# Oplader.net
KiCad netlist of a schematic drawn in Altium Designer
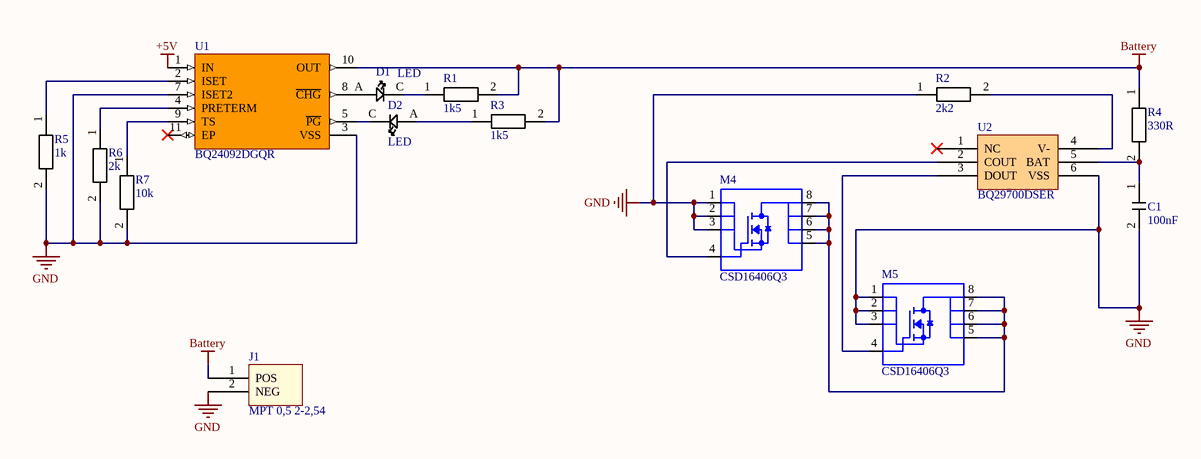
[diagram p0: Oplader.SchDoc]

(export (version "E")
  (design (tool "Eeschema 10.0.6"))
  (components
    (comp (ref "C1") (value "100nF") (footprint "0603") (libsource (lib "condensator") (part "Condensator")))
    (comp (ref "D1") (value "LED") (footprint "LED") (libsource (lib "Schlib1") (part "LED")))
    (comp (ref "D2") (value "LED") (footprint "LED") (libsource (lib "Schlib1") (part "LED")))
    (comp (ref "J1")
      (value "MPT 0,5 2-2,54")
      (footprint "MPT 0,5 2-2,54")
      (libsource (lib "Schlib1") (part "MPT 0,5 2-2,54"))
    )
    (comp (ref "M4")
      (value "CSD16406Q3")
      (footprint "CSD16406Q3")
      (libsource (lib "Schlib1") (part "CSD16406Q3"))
    )
    (comp (ref "M5")
      (value "CSD16406Q3")
      (footprint "CSD16406Q3")
      (libsource (lib "Schlib1") (part "CSD16406Q3"))
    )
    (comp (ref "R1") (value "1k5") (footprint "0603") (libsource (lib "weerstand") (part "weerstand")))
    (comp (ref "R2") (value "2k2") (footprint "0603") (libsource (lib "weerstand") (part "weerstand")))
    (comp (ref "R3") (value "1k5") (footprint "0603") (libsource (lib "weerstand") (part "weerstand")))
    (comp (ref "R4") (value "330R") (footprint "0603") (libsource (lib "weerstand") (part "weerstand")))
    (comp (ref "R5") (value "1k") (footprint "0603") (libsource (lib "weerstand") (part "weerstand")))
    (comp (ref "R6") (value "2k") (footprint "0603") (libsource (lib "weerstand") (part "weerstand")))
    (comp (ref "R7") (value "10k") (footprint "0603") (libsource (lib "weerstand") (part "weerstand")))
    (comp (ref "U1")
      (value "BQ24092DGQR")
      (footprint "BQ24092DGQR")
      (libsource (lib "Schlib1") (part "BQ24092DGQR"))
    )
    (comp (ref "U2")
      (value "BQ29700DSER")
      (footprint "BQ29700DSER")
      (libsource (lib "Schlib1") (part "BQ29700DSER"))
    )
  )
  (nets
    (net (code "1") (name "+5V") (class "Default")
      (node (ref "U1") (pin "1") (pinfunction "IN_1") (pintype "input"))
    )
    (net (code "2") (name "Battery") (class "Default")
      (node (ref "J1") (pin "1") (pinfunction "POS_1") (pintype "passive"))
      (node (ref "R1") (pin "2") (pinfunction "G_2") (pintype "passive"))
      (node (ref "R3") (pin "2") (pinfunction "G_2") (pintype "passive"))
      (node (ref "R4") (pin "1") (pinfunction "1_1") (pintype "passive"))
      (node (ref "U1") (pin "10") (pinfunction "OUT_10") (pintype "output"))
    )
    (net (code "3") (name "GND") (class "Default")
      (node (ref "C1") (pin "2") (pinfunction "G_2") (pintype "passive"))
      (node (ref "J1") (pin "2") (pinfunction "NEG_2") (pintype "passive"))
      (node (ref "M4") (pin "1") (pinfunction "S_1_1") (pintype "passive"))
      (node (ref "M4") (pin "2") (pinfunction "S_2_2") (pintype "passive"))
      (node (ref "M4") (pin "3") (pinfunction "S_3_3") (pintype "passive"))
      (node (ref "M5") (pin "1") (pinfunction "S_1_1") (pintype "passive"))
      (node (ref "M5") (pin "2") (pinfunction "S_2_2") (pintype "passive"))
      (node (ref "M5") (pin "3") (pinfunction "S_3_3") (pintype "passive"))
      (node (ref "R2") (pin "1") (pinfunction "1_1") (pintype "passive"))
      (node (ref "R5") (pin "2") (pinfunction "G_2") (pintype "passive"))
      (node (ref "R6") (pin "2") (pinfunction "G_2") (pintype "passive"))
      (node (ref "R7") (pin "2") (pinfunction "G_2") (pintype "passive"))
      (node (ref "U1") (pin "3") (pinfunction "VSS_3") (pintype "power_in"))
      (node (ref "U1") (pin "7") (pinfunction "ISET2_7") (pintype "input"))
      (node (ref "U2") (pin "6") (pinfunction "VSS_6") (pintype "passive"))
    )
    (net (code "4") (name "Net-(D1-PadC)") (class "Default")
      (node (ref "D1") (pin "C") (pinfunction "C_C") (pintype "passive"))
      (node (ref "R1") (pin "1") (pinfunction "1_1") (pintype "passive"))
    )
    (net (code "5") (name "Net-(D2-PadA)") (class "Default")
      (node (ref "D2") (pin "A") (pinfunction "A_A") (pintype "passive"))
      (node (ref "R3") (pin "1") (pinfunction "1_1") (pintype "passive"))
    )
    (net (code "6") (name "Net-(M4-D_5)") (class "Default")
      (node (ref "M4") (pin "5") (pinfunction "D_5_5") (pintype "passive"))
      (node (ref "M4") (pin "6") (pinfunction "D_6_6") (pintype "passive"))
      (node (ref "M4") (pin "7") (pinfunction "D_7_7") (pintype "passive"))
      (node (ref "M4") (pin "8") (pinfunction "D_8_8") (pintype "passive"))
      (node (ref "M5") (pin "5") (pinfunction "D_5_5") (pintype "passive"))
      (node (ref "M5") (pin "6") (pinfunction "D_6_6") (pintype "passive"))
      (node (ref "M5") (pin "7") (pinfunction "D_7_7") (pintype "passive"))
      (node (ref "M5") (pin "8") (pinfunction "D_8_8") (pintype "passive"))
    )
    (net (code "7") (name "Net-(M4-G)") (class "Default")
      (node (ref "M4") (pin "4") (pinfunction "G_4") (pintype "passive"))
      (node (ref "U2") (pin "2") (pinfunction "COUT_2") (pintype "passive"))
    )
    (net (code "8") (name "Net-(M5-G)") (class "Default")
      (node (ref "M5") (pin "4") (pinfunction "G_4") (pintype "passive"))
      (node (ref "U2") (pin "3") (pinfunction "DOUT_3") (pintype "passive"))
    )
    (net (code "9") (name "Net-(R2-G)") (class "Default")
      (node (ref "R2") (pin "2") (pinfunction "G_2") (pintype "passive"))
      (node (ref "U2") (pin "4") (pinfunction "V-_4") (pintype "passive"))
    )
    (net (code "10") (name "Net-(R4-G)") (class "Default")
      (node (ref "C1") (pin "1") (pinfunction "G_1") (pintype "passive"))
      (node (ref "R4") (pin "2") (pinfunction "G_2") (pintype "passive"))
      (node (ref "U2") (pin "5") (pinfunction "BAT_5") (pintype "passive"))
    )
    (net (code "11") (name "Net-(U1-ISET)") (class "Default")
      (node (ref "R5") (pin "1") (pinfunction "1_1") (pintype "passive"))
      (node (ref "U1") (pin "2") (pinfunction "ISET_2") (pintype "input"))
    )
    (net (code "12") (name "Net-(U1-PRETERM)") (class "Default")
      (node (ref "R6") (pin "1") (pinfunction "1_1") (pintype "passive"))
      (node (ref "U1") (pin "4") (pinfunction "PRETERM_4") (pintype "input"))
    )
    (net (code "13") (name "Net-(U1-TS)") (class "Default")
      (node (ref "R7") (pin "1") (pinfunction "1_1") (pintype "passive"))
      (node (ref "U1") (pin "9") (pinfunction "TS_9") (pintype "input"))
    )
    (net (code "14") (name "Net-(U1-~{CHG})") (class "Default")
      (node (ref "D1") (pin "A") (pinfunction "A_A") (pintype "passive"))
      (node (ref "U1") (pin "8") (pinfunction "~{CHG}_8") (pintype "output"))
    )
    (net (code "15") (name "Net-(U1-~{PG})") (class "Default")
      (node (ref "D2") (pin "C") (pinfunction "C_C") (pintype "passive"))
      (node (ref "U1") (pin "5") (pinfunction "~{PG}_5") (pintype "output"))
    )
    (net (code "16") (name "unconnected-(U1-EP-Pad11)") (class "Default")
      (node (ref "U1") (pin "11") (pinfunction "EP_11") (pintype "bidirectional+no_connect"))
    )
    (net (code "17") (name "unconnected-(U2-NC-Pad1)") (class "Default")
      (node (ref "U2") (pin "1") (pinfunction "NC_1") (pintype "passive+no_connect"))
    )
  )
)
